# SCH_DHT22_TEMP_SENSOR_2024-02-15.net
KiCad netlist of a schematic drawn in EasyEDA
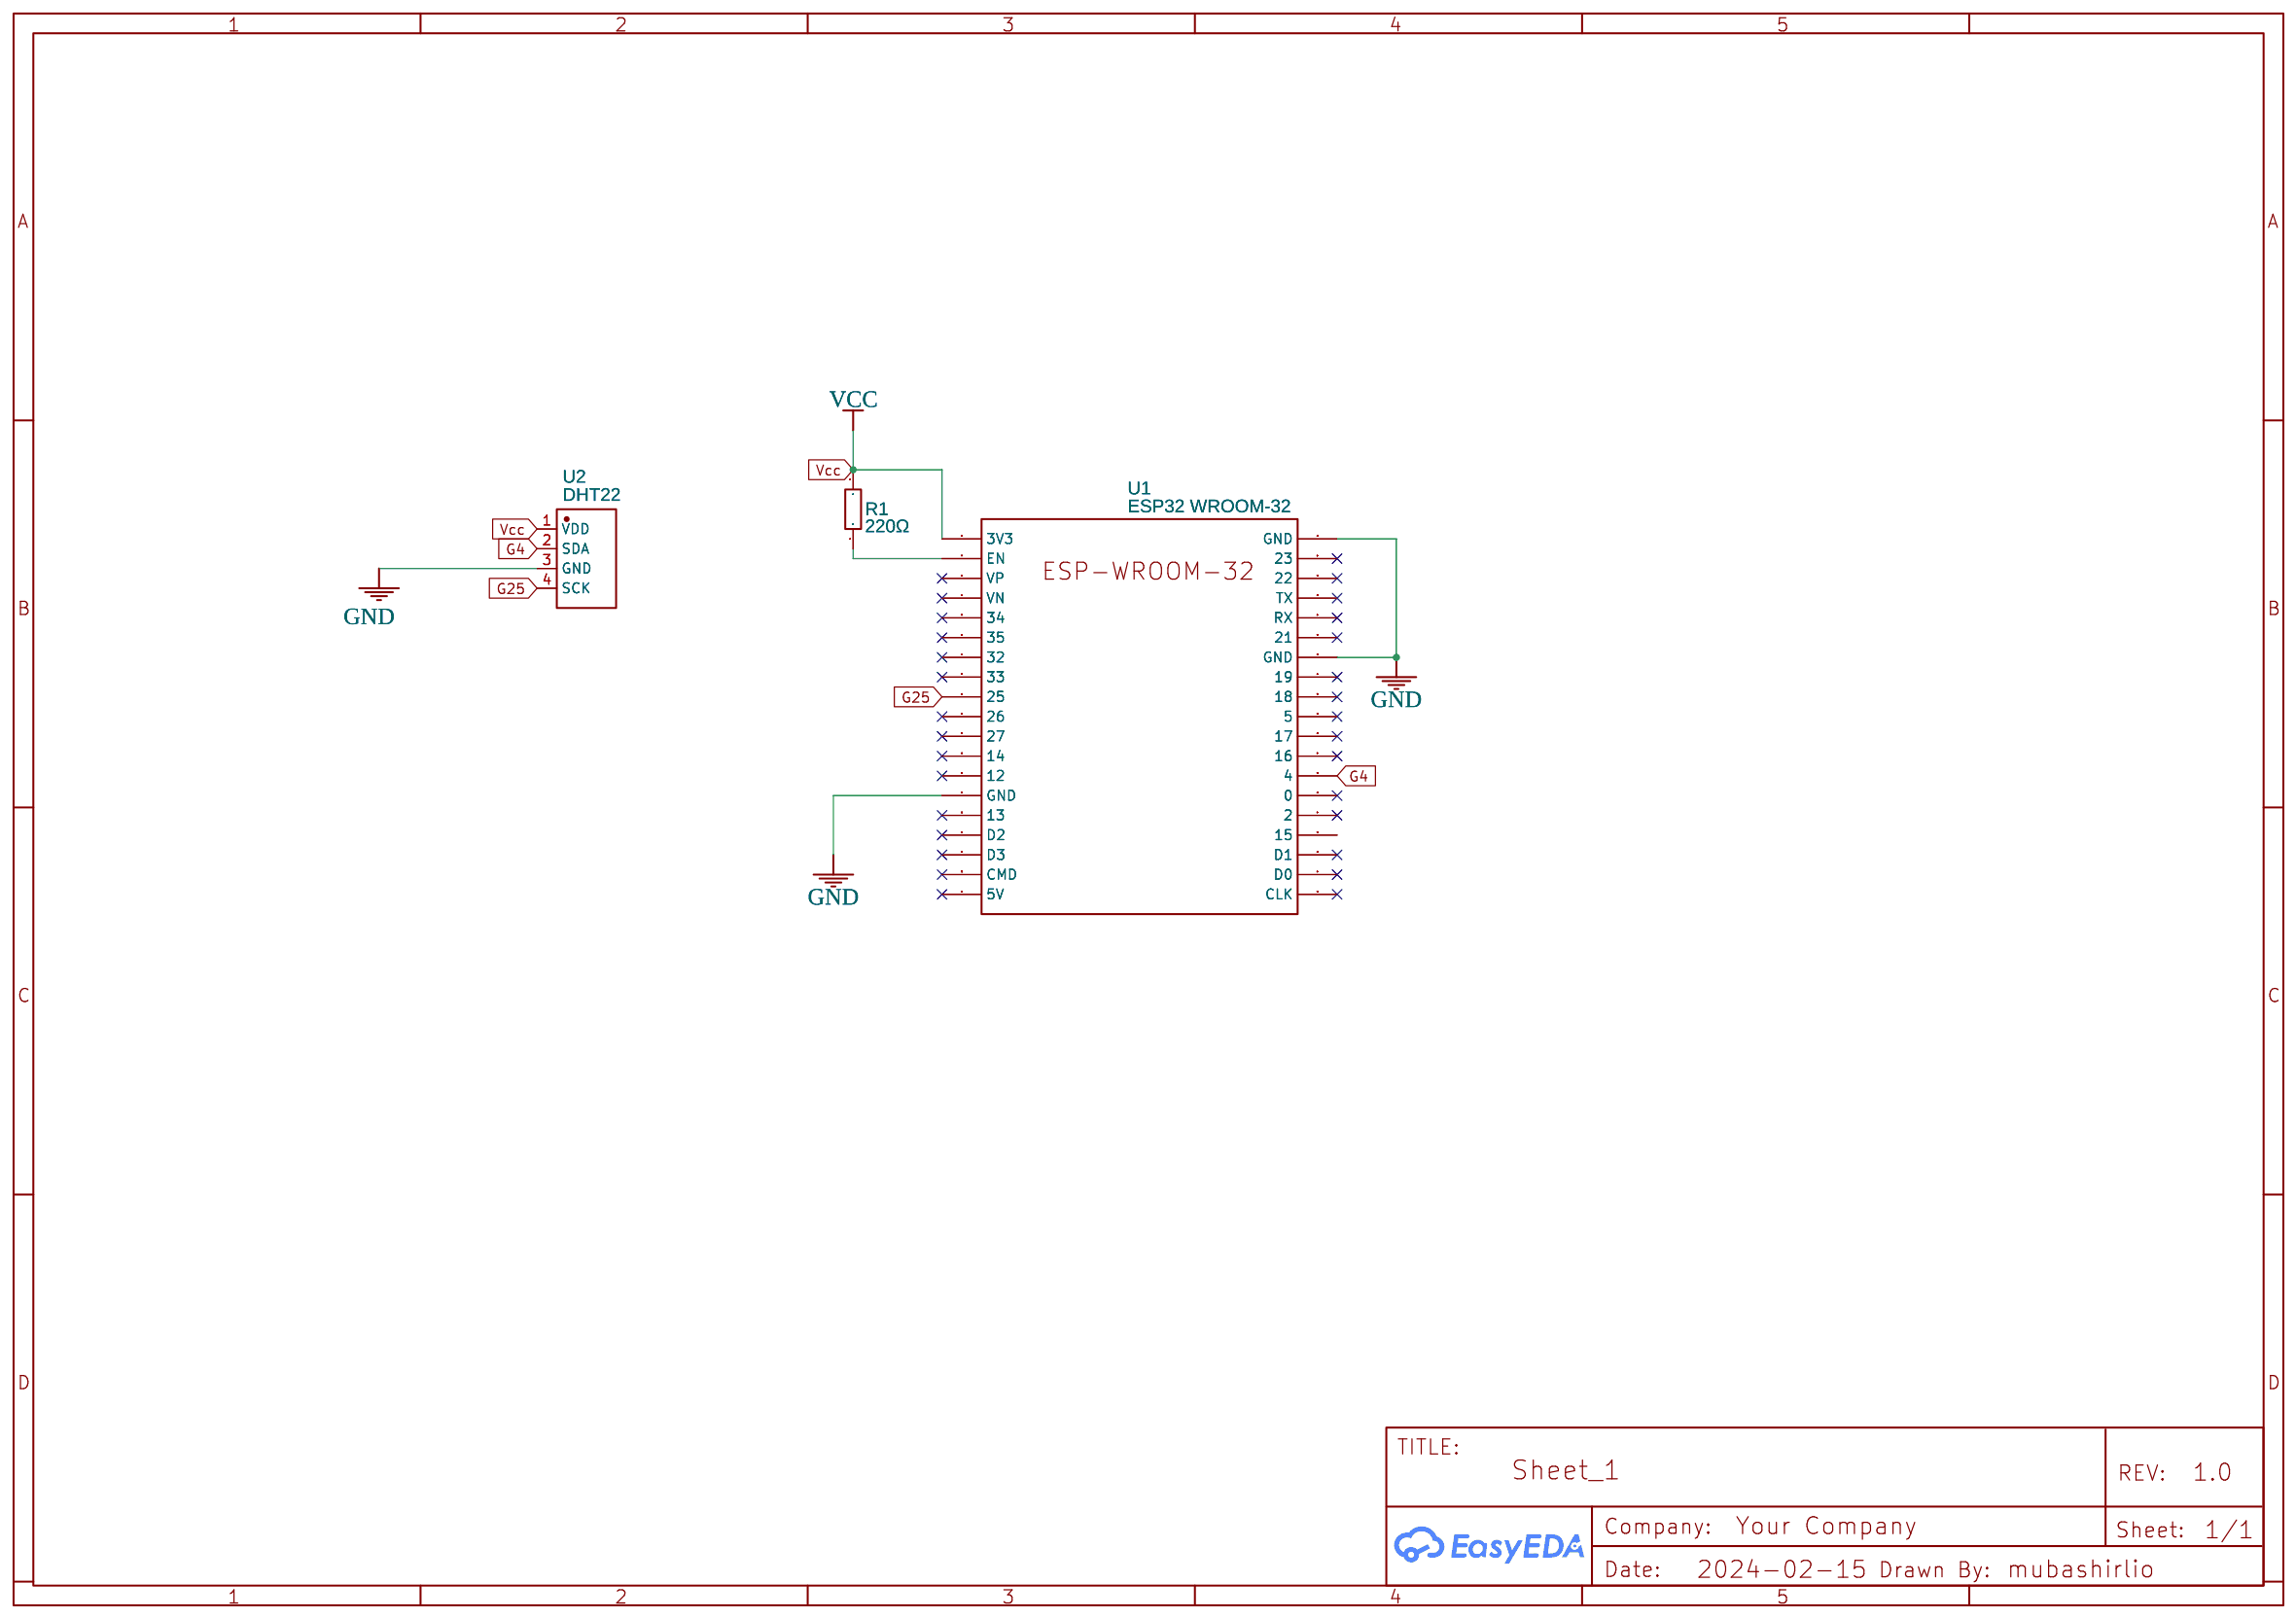
[diagram p0: schematic sheet]

(export (version "E")
  (design (tool "Eeschema 10.0.6"))
  (components
    (comp (ref "R1")
      (value "220Ω")
      (fields (field (name "Manufacturer Part") "RT0805DRD07220RL") (field (name "Manufacturer") "YAGEO(国巨)"))
      (libsource (lib "") (part "RT0805DRD07220RL"))
    )
    (comp (ref "U1") (value "ESP32 WROOM-32") (libsource (lib "") (part "ESP32 WROOM-32")))
    (comp (ref "U2")
      (value "DHT22")
      (fields (field (name "Manufacturer") "HAIGU(广州海谷)"))
      (libsource (lib "") (part "DHT22"))
    )
  )
  (nets
    (net (code "1") (name "G4") (class "Default")
      (node (ref "U1") (pin "26") (pinfunction "4_26") (pintype "unspecified"))
      (node (ref "U2") (pin "2") (pinfunction "SDA_2") (pintype "unspecified"))
    )
    (net (code "2") (name "G25") (class "Default")
      (node (ref "U1") (pin "9") (pinfunction "25_9") (pintype "unspecified"))
      (node (ref "U2") (pin "4") (pinfunction "SCK_4") (pintype "unspecified"))
    )
    (net (code "3") (name "GND") (class "Default")
      (node (ref "U1") (pin "14") (pinfunction "GND_14") (pintype "unspecified"))
      (node (ref "U1") (pin "32") (pinfunction "GND_32") (pintype "unspecified"))
      (node (ref "U1") (pin "38") (pinfunction "GND_38") (pintype "unspecified"))
      (node (ref "U2") (pin "3") (pinfunction "GND_3") (pintype "unspecified"))
    )
    (net (code "4") (name "Net-(U1-EN)") (class "Default")
      (node (ref "R1") (pin "1") (pinfunction "1_1") (pintype "unspecified"))
      (node (ref "U1") (pin "2") (pinfunction "EN_2") (pintype "unspecified"))
    )
    (net (code "5") (name "Vcc") (class "Default")
      (node (ref "R1") (pin "2") (pinfunction "2_2") (pintype "unspecified"))
      (node (ref "U1") (pin "1") (pinfunction "3V3_1") (pintype "unspecified"))
      (node (ref "U2") (pin "1") (pinfunction "VDD_1") (pintype "unspecified"))
    )
    (net (code "6") (name "unconnected-(U1-0-Pad25)") (class "Default")
      (node (ref "U1") (pin "25") (pinfunction "0_25") (pintype "unspecified+no_connect"))
    )
    (net (code "7") (name "unconnected-(U1-2-Pad24)") (class "Default")
      (node (ref "U1") (pin "24") (pinfunction "2_24") (pintype "unspecified+no_connect"))
    )
    (net (code "8") (name "unconnected-(U1-5-Pad29)") (class "Default")
      (node (ref "U1") (pin "29") (pinfunction "5_29") (pintype "unspecified+no_connect"))
    )
    (net (code "9") (name "unconnected-(U1-5V-Pad19)") (class "Default")
      (node (ref "U1") (pin "19") (pinfunction "5V_19") (pintype "unspecified+no_connect"))
    )
    (net (code "10") (name "unconnected-(U1-12-Pad13)") (class "Default")
      (node (ref "U1") (pin "13") (pinfunction "12_13") (pintype "unspecified+no_connect"))
    )
    (net (code "11") (name "unconnected-(U1-13-Pad15)") (class "Default")
      (node (ref "U1") (pin "15") (pinfunction "13_15") (pintype "unspecified+no_connect"))
    )
    (net (code "12") (name "unconnected-(U1-14-Pad12)") (class "Default")
      (node (ref "U1") (pin "12") (pinfunction "14_12") (pintype "unspecified+no_connect"))
    )
    (net (code "13") (name "unconnected-(U1-15-Pad23)") (class "Default")
      (node (ref "U1") (pin "23") (pinfunction "15_23") (pintype "unspecified"))
    )
    (net (code "14") (name "unconnected-(U1-16-Pad27)") (class "Default")
      (node (ref "U1") (pin "27") (pinfunction "16_27") (pintype "unspecified+no_connect"))
    )
    (net (code "15") (name "unconnected-(U1-17-Pad28)") (class "Default")
      (node (ref "U1") (pin "28") (pinfunction "17_28") (pintype "unspecified+no_connect"))
    )
    (net (code "16") (name "unconnected-(U1-18-Pad30)") (class "Default")
      (node (ref "U1") (pin "30") (pinfunction "18_30") (pintype "unspecified+no_connect"))
    )
    (net (code "17") (name "unconnected-(U1-19-Pad31)") (class "Default")
      (node (ref "U1") (pin "31") (pinfunction "19_31") (pintype "unspecified+no_connect"))
    )
    (net (code "18") (name "unconnected-(U1-21-Pad33)") (class "Default")
      (node (ref "U1") (pin "33") (pinfunction "21_33") (pintype "unspecified+no_connect"))
    )
    (net (code "19") (name "unconnected-(U1-22-Pad36)") (class "Default")
      (node (ref "U1") (pin "36") (pinfunction "22_36") (pintype "unspecified+no_connect"))
    )
    (net (code "20") (name "unconnected-(U1-23-Pad37)") (class "Default")
      (node (ref "U1") (pin "37") (pinfunction "23_37") (pintype "unspecified+no_connect"))
    )
    (net (code "21") (name "unconnected-(U1-26-Pad10)") (class "Default")
      (node (ref "U1") (pin "10") (pinfunction "26_10") (pintype "unspecified+no_connect"))
    )
    (net (code "22") (name "unconnected-(U1-27-Pad11)") (class "Default")
      (node (ref "U1") (pin "11") (pinfunction "27_11") (pintype "unspecified+no_connect"))
    )
    (net (code "23") (name "unconnected-(U1-32-Pad7)") (class "Default")
      (node (ref "U1") (pin "7") (pinfunction "32_7") (pintype "unspecified+no_connect"))
    )
    (net (code "24") (name "unconnected-(U1-33-Pad8)") (class "Default")
      (node (ref "U1") (pin "8") (pinfunction "33_8") (pintype "unspecified+no_connect"))
    )
    (net (code "25") (name "unconnected-(U1-34-Pad5)") (class "Default")
      (node (ref "U1") (pin "5") (pinfunction "34_5") (pintype "unspecified+no_connect"))
    )
    (net (code "26") (name "unconnected-(U1-35-Pad6)") (class "Default")
      (node (ref "U1") (pin "6") (pinfunction "35_6") (pintype "unspecified+no_connect"))
    )
    (net (code "27") (name "unconnected-(U1-CLK-Pad20)") (class "Default")
      (node (ref "U1") (pin "20") (pinfunction "CLK_20") (pintype "unspecified+no_connect"))
    )
    (net (code "28") (name "unconnected-(U1-CMD-Pad18)") (class "Default")
      (node (ref "U1") (pin "18") (pinfunction "CMD_18") (pintype "unspecified+no_connect"))
    )
    (net (code "29") (name "unconnected-(U1-D0-Pad21)") (class "Default")
      (node (ref "U1") (pin "21") (pinfunction "D0_21") (pintype "unspecified+no_connect"))
    )
    (net (code "30") (name "unconnected-(U1-D1-Pad22)") (class "Default")
      (node (ref "U1") (pin "22") (pinfunction "D1_22") (pintype "unspecified+no_connect"))
    )
    (net (code "31") (name "unconnected-(U1-D2-Pad16)") (class "Default")
      (node (ref "U1") (pin "16") (pinfunction "D2_16") (pintype "unspecified+no_connect"))
    )
    (net (code "32") (name "unconnected-(U1-D3-Pad17)") (class "Default")
      (node (ref "U1") (pin "17") (pinfunction "D3_17") (pintype "unspecified+no_connect"))
    )
    (net (code "33") (name "unconnected-(U1-RX-Pad34)") (class "Default")
      (node (ref "U1") (pin "34") (pinfunction "RX_34") (pintype "unspecified+no_connect"))
    )
    (net (code "34") (name "unconnected-(U1-TX-Pad35)") (class "Default")
      (node (ref "U1") (pin "35") (pinfunction "TX_35") (pintype "unspecified+no_connect"))
    )
    (net (code "35") (name "unconnected-(U1-VN-Pad4)") (class "Default")
      (node (ref "U1") (pin "4") (pinfunction "VN_4") (pintype "unspecified+no_connect"))
    )
    (net (code "36") (name "unconnected-(U1-VP-Pad3)") (class "Default")
      (node (ref "U1") (pin "3") (pinfunction "VP_3") (pintype "unspecified+no_connect"))
    )
  )
)
